# 01_-_MCU.net
KiCad netlist of a schematic drawn in Altium Designer
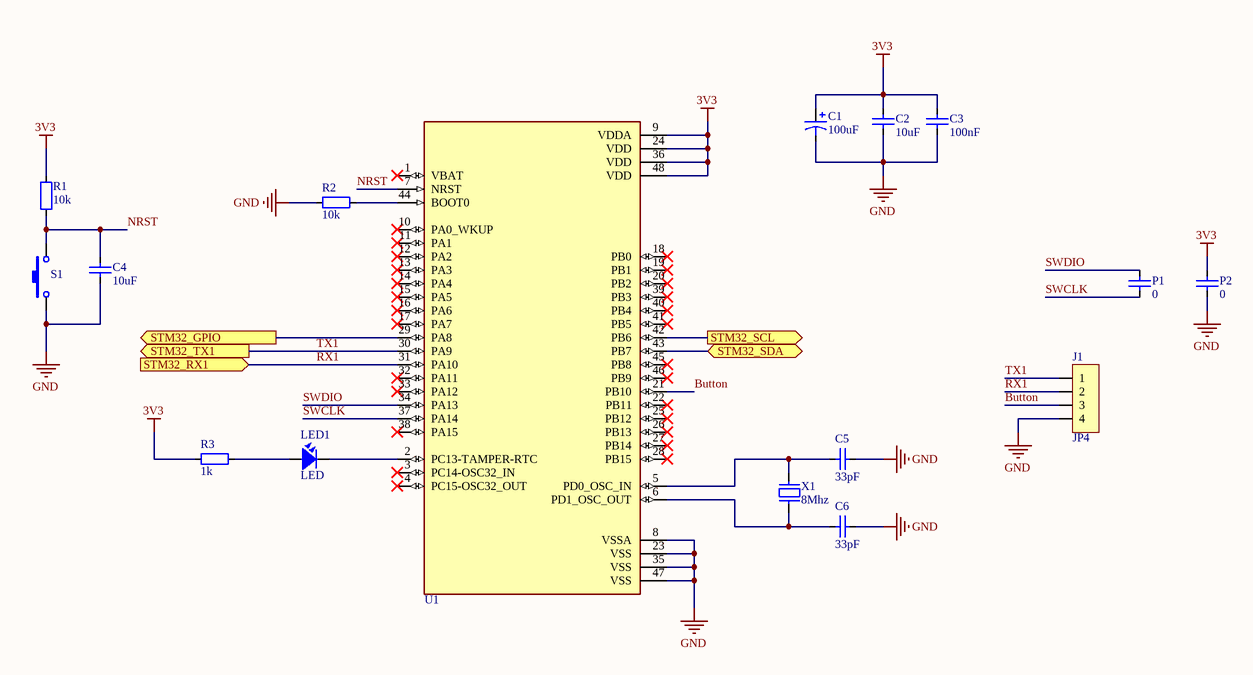
[diagram p0: [01] - MCU.SchDoc]

(export (version "E")
  (design (tool "Eeschema 10.0.6"))
  (components
    (comp (ref "C1")
      (value "100uF")
      (footprint "CAP_7343")
      (description "Tantalum")
      (fields (field (name "PUBLISHER") "Altium Limited"))
      (libsource (lib "My Library") (part "Cap Pol"))
    )
    (comp (ref "C2")
      (value "10uF")
      (footprint "CAP_0603")
      (description "Capacitor")
      (fields (field (name "PUBLISHER") "Altium Limited"))
      (libsource (lib "My Library") (part "CapSMD"))
    )
    (comp (ref "C3")
      (value "100nF")
      (footprint "CAP_0603")
      (description "Capacitor")
      (fields (field (name "PUBLISHER") "Altium Limited"))
      (libsource (lib "My Library") (part "CapSMD"))
    )
    (comp (ref "C4")
      (value "10uF")
      (footprint "CAP_0603")
      (description "Capacitor")
      (fields (field (name "PUBLISHER") "Altium Limited"))
      (libsource (lib "My Library") (part "CapSMD"))
    )
    (comp (ref "C5")
      (value "33pF")
      (footprint "CAP_0603")
      (description "Capacitor")
      (fields (field (name "PUBLISHER") "Altium Limited"))
      (libsource (lib "My Library") (part "CapSMD"))
    )
    (comp (ref "C6")
      (value "33pF")
      (footprint "CAP_0603")
      (description "Capacitor")
      (fields (field (name "PUBLISHER") "Altium Limited"))
      (libsource (lib "My Library") (part "CapSMD"))
    )
    (comp (ref "J1")
      (value "JP4")
      (footprint "JP4-C1T")
      (description "WR-PHD 2.54 mm Angled Socket Header")
      (fields
        (field (name "MANUFACTURER") "Würth Elektronik eiSos GmbH")
        (field (name "PARTNO") "613004143121")
        (field (name "CREATED BY") "Karrer Zheng")
      )
      (libsource (lib "My Library") (part "JP4"))
    )
    (comp (ref "LED1")
      (value "LED")
      (footprint "LED-0805-Orange")
      (description "LED Single colour Green and Red")
      (libsource (lib "My Library") (part "LED"))
    )
    (comp (ref "P1")
      (value "0")
      (footprint "CAP_0805")
      (description "Pad")
      (fields (field (name "PUBLISHER") "Altium Limited"))
      (libsource (lib "My Library") (part "CapSMD"))
    )
    (comp (ref "P2")
      (value "0")
      (footprint "CAP_0805")
      (description "Pad")
      (fields (field (name "PUBLISHER") "Altium Limited"))
      (libsource (lib "My Library") (part "CapSMD"))
    )
    (comp (ref "R1")
      (value "10k")
      (footprint "RES-SMD-0603")
      (description "Resistor")
      (fields
        (field (name "MANUFACTURER") "Generic Components")
        (field (name "PUBLISHER") "Altium Hobart Technology Centre")
      )
      (libsource (lib "My Library") (part "Resistor - SMD"))
    )
    (comp (ref "R2")
      (value "10k")
      (footprint "RES-SMD-0603")
      (description "Resistor")
      (fields
        (field (name "MANUFACTURER") "Generic Components")
        (field (name "PUBLISHER") "Altium Hobart Technology Centre")
      )
      (libsource (lib "My Library") (part "Resistor - SMD"))
    )
    (comp (ref "R3")
      (value "1k")
      (footprint "RES-SMD-0603")
      (description "Resistor")
      (fields
        (field (name "MANUFACTURER") "Generic Components")
        (field (name "PUBLISHER") "Altium Hobart Technology Centre")
      )
      (libsource (lib "My Library") (part "Resistor - SMD"))
    )
    (comp (ref "S1")
      (value "SW-SMD")
      (footprint "SW 3x2x4")
      (description "Switch")
      (fields (field (name "PUBLISHER") "Altium Limited"))
      (libsource (lib "My Library") (part "SW-SMD"))
    )
    (comp (ref "U1")
      (value "STM32")
      (footprint "LQFP 48")
      (description "STM32 ARM-based 32-bit MCU with 64 Kbytes Flash, 64-pin LQFP, Industrial Temperature")
      (libsource (lib "My Library") (part "STM32F103C8T6"))
    )
    (comp (ref "X1")
      (value "8Mhz")
      (footprint "XTAL 5032 SMD")
      (description "Crystal For all Crystal 2pin.")
      (libsource (lib "My Library") (part "XT2"))
    )
  )
  (nets
    (net (code "1") (name "/Button") (class "Default")
      (node (ref "J1") (pin "3") (pinfunction "3_3") (pintype "passive"))
      (node (ref "U1") (pin "21") (pinfunction "PB10_21") (pintype "bidirectional"))
    )
    (net (code "2") (name "/NRST") (class "Default")
      (node (ref "C4") (pin "2") (pinfunction "2_2") (pintype "passive"))
      (node (ref "R1") (pin "1") (pinfunction "1_1") (pintype "passive"))
      (node (ref "S1") (pin "2") (pinfunction "2_2") (pintype "passive"))
      (node (ref "U1") (pin "7") (pinfunction "NRST_7") (pintype "input"))
    )
    (net (code "3") (name "/RX1") (class "Default")
      (node (ref "J1") (pin "2") (pinfunction "2_2") (pintype "passive"))
      (node (ref "U1") (pin "31") (pinfunction "PA10_31") (pintype "bidirectional"))
    )
    (net (code "4") (name "/STM32_GPIO") (class "Default")
      (node (ref "U1") (pin "29") (pinfunction "PA8_29") (pintype "bidirectional"))
    )
    (net (code "5") (name "/STM32_SCL") (class "Default")
      (node (ref "U1") (pin "42") (pinfunction "PB6_42") (pintype "bidirectional"))
    )
    (net (code "6") (name "/STM32_SDA") (class "Default")
      (node (ref "U1") (pin "43") (pinfunction "PB7_43") (pintype "bidirectional"))
    )
    (net (code "7") (name "/SWCLK") (class "Default")
      (node (ref "P1") (pin "1") (pinfunction "1_1") (pintype "passive"))
      (node (ref "U1") (pin "37") (pinfunction "PA14_37") (pintype "bidirectional"))
    )
    (net (code "8") (name "/SWDIO") (class "Default")
      (node (ref "P1") (pin "2") (pinfunction "2_2") (pintype "passive"))
      (node (ref "U1") (pin "34") (pinfunction "PA13_34") (pintype "bidirectional"))
    )
    (net (code "9") (name "/TX1") (class "Default")
      (node (ref "J1") (pin "1") (pinfunction "1_1") (pintype "passive"))
      (node (ref "U1") (pin "30") (pinfunction "PA9_30") (pintype "bidirectional"))
    )
    (net (code "10") (name "3V3") (class "Default")
      (node (ref "C1") (pin "1") (pinfunction "1_1") (pintype "passive"))
      (node (ref "C2") (pin "2") (pinfunction "2_2") (pintype "passive"))
      (node (ref "C3") (pin "2") (pinfunction "2_2") (pintype "passive"))
      (node (ref "P2") (pin "2") (pinfunction "2_2") (pintype "passive"))
      (node (ref "R1") (pin "2") (pinfunction "2_2") (pintype "passive"))
      (node (ref "R3") (pin "1") (pinfunction "1_1") (pintype "passive"))
      (node (ref "U1") (pin "24") (pinfunction "VDD_24") (pintype "power_in"))
      (node (ref "U1") (pin "36") (pinfunction "VDD_36") (pintype "power_in"))
      (node (ref "U1") (pin "48") (pinfunction "VDD_48") (pintype "power_in"))
      (node (ref "U1") (pin "9") (pinfunction "VDDA_9") (pintype "power_in"))
    )
    (net (code "11") (name "GND") (class "Default")
      (node (ref "C1") (pin "2") (pinfunction "2_2") (pintype "passive"))
      (node (ref "C2") (pin "1") (pinfunction "1_1") (pintype "passive"))
      (node (ref "C3") (pin "1") (pinfunction "1_1") (pintype "passive"))
      (node (ref "C4") (pin "1") (pinfunction "1_1") (pintype "passive"))
      (node (ref "C5") (pin "2") (pinfunction "2_2") (pintype "passive"))
      (node (ref "C6") (pin "2") (pinfunction "2_2") (pintype "passive"))
      (node (ref "J1") (pin "4") (pinfunction "4_4") (pintype "passive"))
      (node (ref "P2") (pin "1") (pinfunction "1_1") (pintype "passive"))
      (node (ref "R2") (pin "1") (pinfunction "1_1") (pintype "passive"))
      (node (ref "S1") (pin "1") (pinfunction "1_1") (pintype "passive"))
      (node (ref "U1") (pin "23") (pinfunction "VSS_23") (pintype "power_in"))
      (node (ref "U1") (pin "35") (pinfunction "VSS_35") (pintype "power_in"))
      (node (ref "U1") (pin "47") (pinfunction "VSS_47") (pintype "power_in"))
      (node (ref "U1") (pin "8") (pinfunction "VSSA_8") (pintype "power_in"))
    )
    (net (code "12") (name "Net-(LED1-Pad1)") (class "Default")
      (node (ref "LED1") (pin "1") (pinfunction "1_1") (pintype "passive"))
      (node (ref "R3") (pin "2") (pinfunction "2_2") (pintype "passive"))
    )
    (net (code "13") (name "Net-(U1-BOOT0)") (class "Default")
      (node (ref "R2") (pin "2") (pinfunction "2_2") (pintype "passive"))
      (node (ref "U1") (pin "44") (pinfunction "BOOT0_44") (pintype "input"))
    )
    (net (code "14") (name "Net-(U1-PC13-TAMPER-RTC)") (class "Default")
      (node (ref "LED1") (pin "2") (pinfunction "2_2") (pintype "passive"))
      (node (ref "U1") (pin "2") (pinfunction "PC13-TAMPER-RTC_2") (pintype "bidirectional"))
    )
    (net (code "15") (name "Net-(U1-PD0_OSC_IN)") (class "Default")
      (node (ref "C5") (pin "1") (pinfunction "1_1") (pintype "passive"))
      (node (ref "U1") (pin "5") (pinfunction "PD0_OSC_IN_5") (pintype "bidirectional"))
      (node (ref "X1") (pin "2") (pinfunction "2_2") (pintype "passive"))
    )
    (net (code "16") (name "Net-(U1-PD1_OSC_OUT)") (class "Default")
      (node (ref "C6") (pin "1") (pinfunction "1_1") (pintype "passive"))
      (node (ref "U1") (pin "6") (pinfunction "PD1_OSC_OUT_6") (pintype "bidirectional"))
      (node (ref "X1") (pin "1") (pinfunction "1_1") (pintype "passive"))
    )
    (net (code "17") (name "unconnected-(U1-PA0_WKUP-Pad10)") (class "Default")
      (node (ref "U1") (pin "10") (pinfunction "PA0_WKUP_10") (pintype "bidirectional+no_connect"))
    )
    (net (code "18") (name "unconnected-(U1-PA1-Pad11)") (class "Default")
      (node (ref "U1") (pin "11") (pinfunction "PA1_11") (pintype "bidirectional+no_connect"))
    )
    (net (code "19") (name "unconnected-(U1-PA2-Pad12)") (class "Default")
      (node (ref "U1") (pin "12") (pinfunction "PA2_12") (pintype "bidirectional+no_connect"))
    )
    (net (code "20") (name "unconnected-(U1-PA3-Pad13)") (class "Default")
      (node (ref "U1") (pin "13") (pinfunction "PA3_13") (pintype "bidirectional+no_connect"))
    )
    (net (code "21") (name "unconnected-(U1-PA4-Pad14)") (class "Default")
      (node (ref "U1") (pin "14") (pinfunction "PA4_14") (pintype "bidirectional+no_connect"))
    )
    (net (code "22") (name "unconnected-(U1-PA5-Pad15)") (class "Default")
      (node (ref "U1") (pin "15") (pinfunction "PA5_15") (pintype "bidirectional+no_connect"))
    )
    (net (code "23") (name "unconnected-(U1-PA6-Pad16)") (class "Default")
      (node (ref "U1") (pin "16") (pinfunction "PA6_16") (pintype "bidirectional+no_connect"))
    )
    (net (code "24") (name "unconnected-(U1-PA7-Pad17)") (class "Default")
      (node (ref "U1") (pin "17") (pinfunction "PA7_17") (pintype "bidirectional+no_connect"))
    )
    (net (code "25") (name "unconnected-(U1-PA11-Pad32)") (class "Default")
      (node (ref "U1") (pin "32") (pinfunction "PA11_32") (pintype "bidirectional+no_connect"))
    )
    (net (code "26") (name "unconnected-(U1-PA12-Pad33)") (class "Default")
      (node (ref "U1") (pin "33") (pinfunction "PA12_33") (pintype "bidirectional+no_connect"))
    )
    (net (code "27") (name "unconnected-(U1-PA15-Pad38)") (class "Default")
      (node (ref "U1") (pin "38") (pinfunction "PA15_38") (pintype "bidirectional+no_connect"))
    )
    (net (code "28") (name "unconnected-(U1-PB0-Pad18)") (class "Default")
      (node (ref "U1") (pin "18") (pinfunction "PB0_18") (pintype "bidirectional+no_connect"))
    )
    (net (code "29") (name "unconnected-(U1-PB1-Pad19)") (class "Default")
      (node (ref "U1") (pin "19") (pinfunction "PB1_19") (pintype "bidirectional+no_connect"))
    )
    (net (code "30") (name "unconnected-(U1-PB2-Pad20)") (class "Default")
      (node (ref "U1") (pin "20") (pinfunction "PB2_20") (pintype "bidirectional+no_connect"))
    )
    (net (code "31") (name "unconnected-(U1-PB3-Pad39)") (class "Default")
      (node (ref "U1") (pin "39") (pinfunction "PB3_39") (pintype "bidirectional+no_connect"))
    )
    (net (code "32") (name "unconnected-(U1-PB4-Pad40)") (class "Default")
      (node (ref "U1") (pin "40") (pinfunction "PB4_40") (pintype "bidirectional+no_connect"))
    )
    (net (code "33") (name "unconnected-(U1-PB5-Pad41)") (class "Default")
      (node (ref "U1") (pin "41") (pinfunction "PB5_41") (pintype "bidirectional+no_connect"))
    )
    (net (code "34") (name "unconnected-(U1-PB8-Pad45)") (class "Default")
      (node (ref "U1") (pin "45") (pinfunction "PB8_45") (pintype "bidirectional+no_connect"))
    )
    (net (code "35") (name "unconnected-(U1-PB9-Pad46)") (class "Default")
      (node (ref "U1") (pin "46") (pinfunction "PB9_46") (pintype "bidirectional+no_connect"))
    )
    (net (code "36") (name "unconnected-(U1-PB11-Pad22)") (class "Default")
      (node (ref "U1") (pin "22") (pinfunction "PB11_22") (pintype "bidirectional+no_connect"))
    )
    (net (code "37") (name "unconnected-(U1-PB12-Pad25)") (class "Default")
      (node (ref "U1") (pin "25") (pinfunction "PB12_25") (pintype "bidirectional+no_connect"))
    )
    (net (code "38") (name "unconnected-(U1-PB13-Pad26)") (class "Default")
      (node (ref "U1") (pin "26") (pinfunction "PB13_26") (pintype "bidirectional+no_connect"))
    )
    (net (code "39") (name "unconnected-(U1-PB14-Pad27)") (class "Default")
      (node (ref "U1") (pin "27") (pinfunction "PB14_27") (pintype "bidirectional+no_connect"))
    )
    (net (code "40") (name "unconnected-(U1-PB15-Pad28)") (class "Default")
      (node (ref "U1") (pin "28") (pinfunction "PB15_28") (pintype "bidirectional+no_connect"))
    )
    (net (code "41") (name "unconnected-(U1-PC14-OSC32_IN-Pad3)") (class "Default")
      (node (ref "U1") (pin "3") (pinfunction "PC14-OSC32_IN_3") (pintype "bidirectional+no_connect"))
    )
    (net (code "42") (name "unconnected-(U1-PC15-OSC32_OUT-Pad4)") (class "Default")
      (node (ref "U1") (pin "4") (pinfunction "PC15-OSC32_OUT_4") (pintype "bidirectional+no_connect"))
    )
    (net (code "43") (name "unconnected-(U1-VBAT-Pad1)") (class "Default")
      (node (ref "U1") (pin "1") (pinfunction "VBAT_1") (pintype "bidirectional+no_connect"))
    )
  )
)
